# RWatch.net
KiCad netlist of a schematic drawn in EAGLE
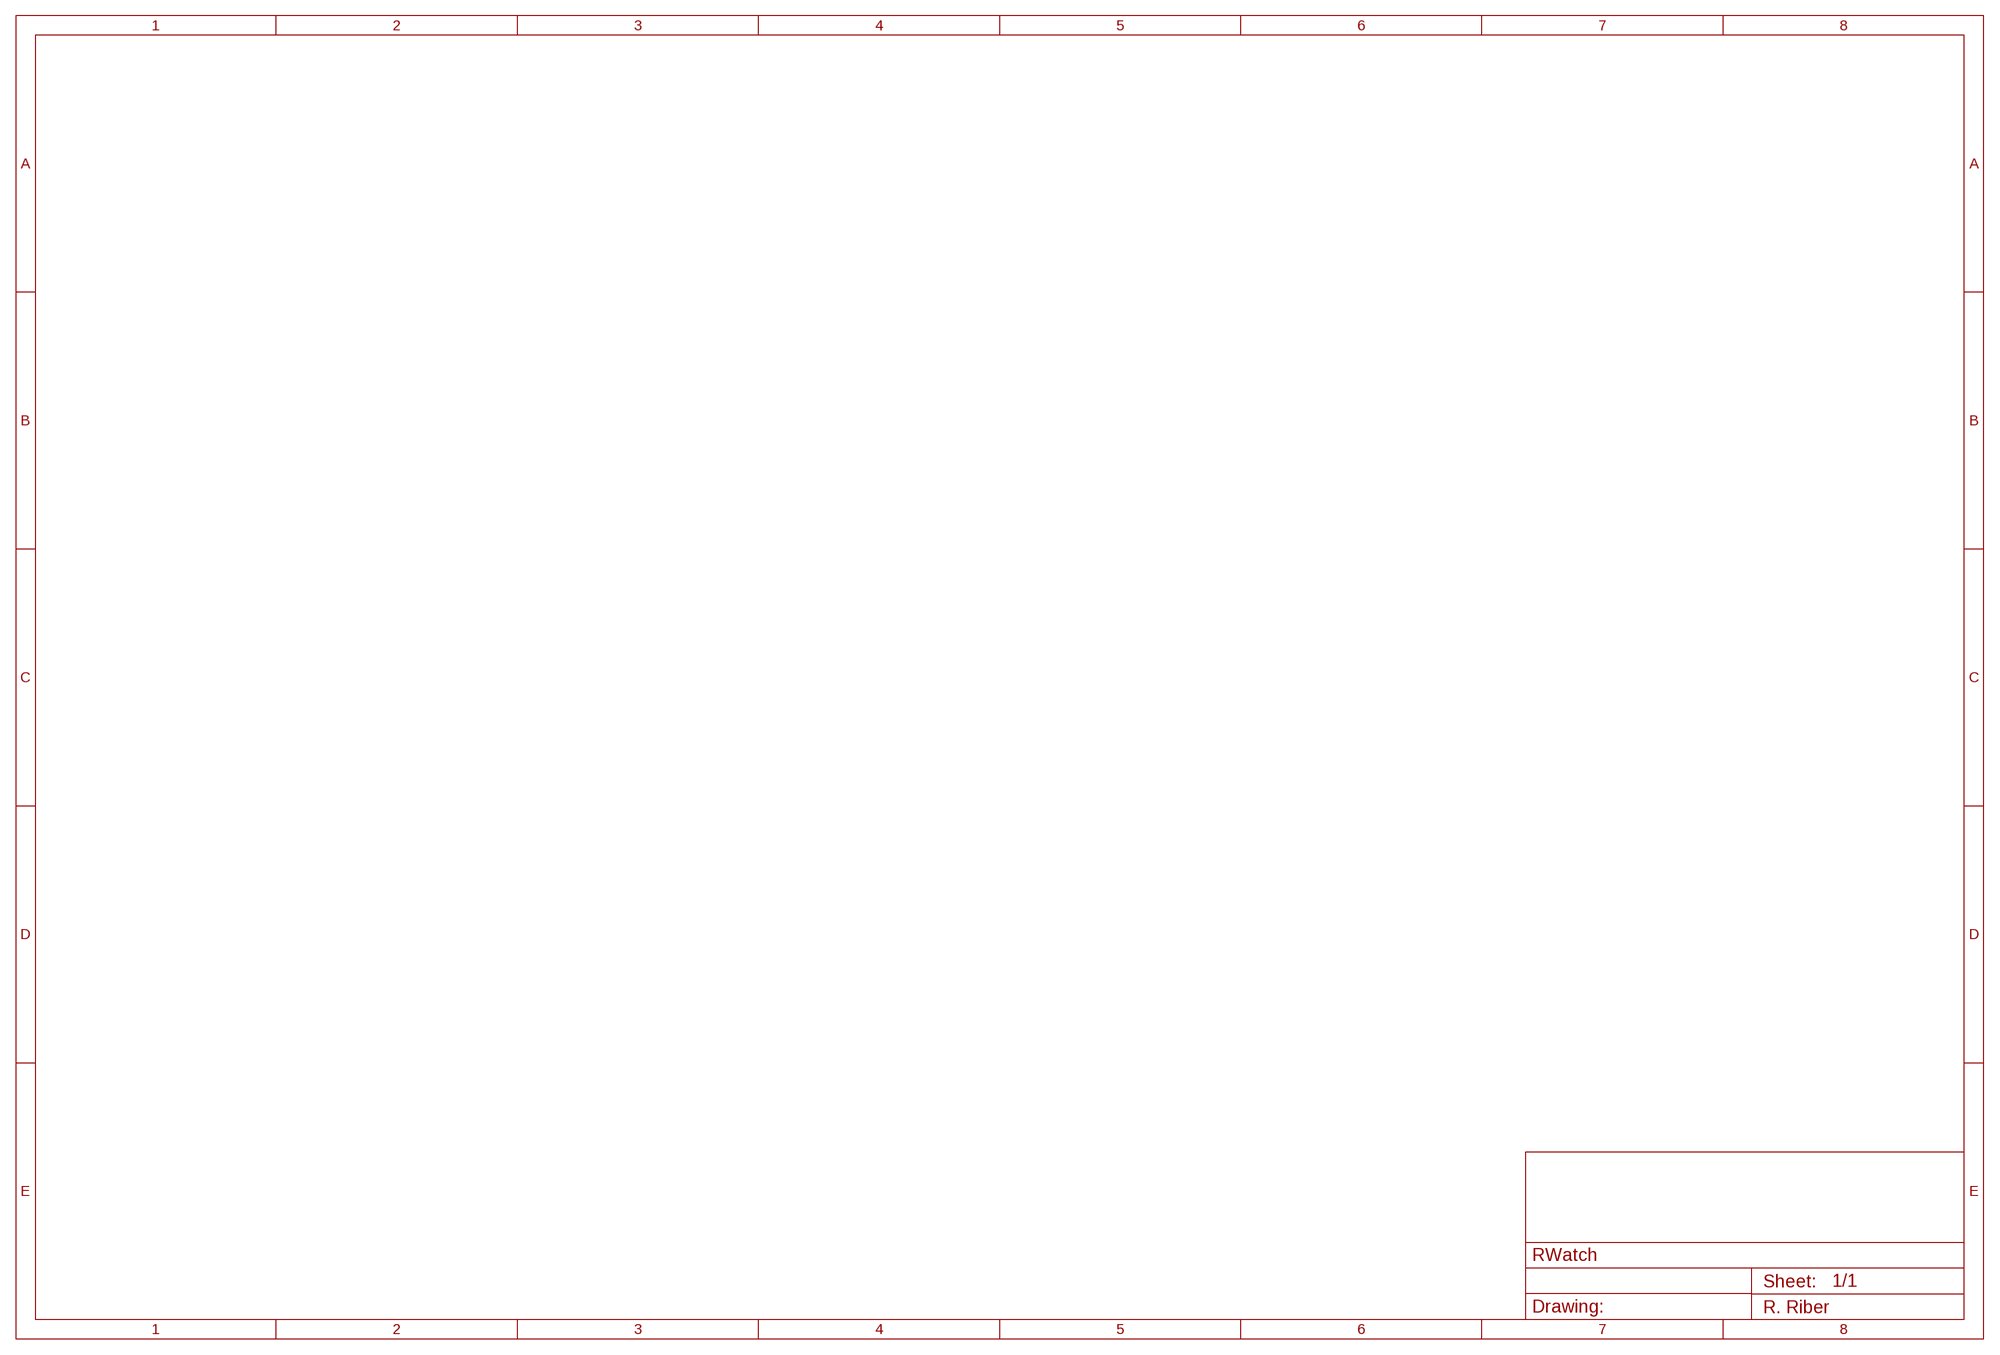
[diagram p0: schematic, sheet 1, part 1 of 2]
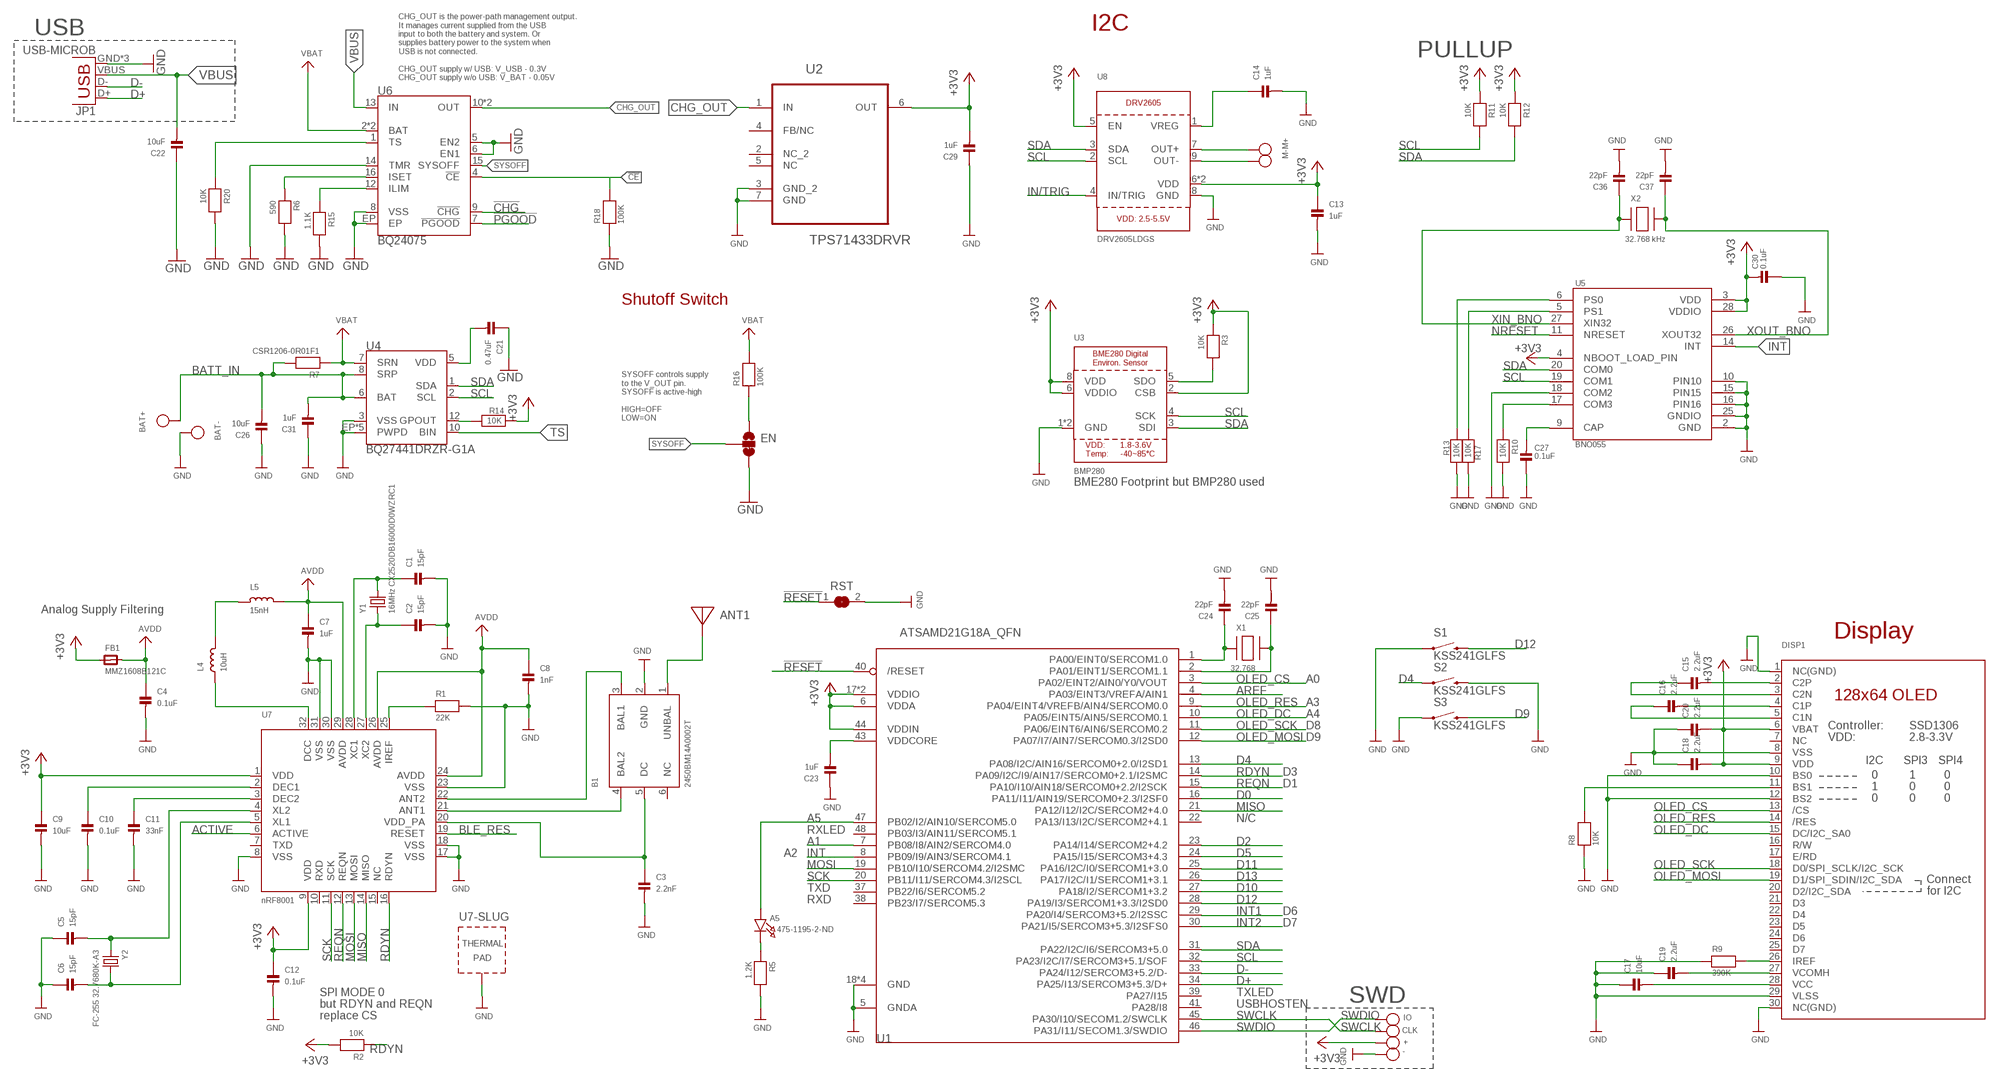
[diagram p1: schematic, sheet 1, part 2 of 2]

(export (version "E")
  (design (tool "Eeschema 10.0.6"))
  (components
    (comp (ref "+")
      (value "TESTPOINTROUND1.5MM")
      (footprint "eagle-import:TESTPOINT_ROUND_1.5MM")
      (libsource (lib "eagle-import") (part "TESTPOINTROUND1.5MM"))
    )
    (comp (ref "-")
      (value "TESTPOINTROUND1.5MM")
      (footprint "eagle-import:TESTPOINT_ROUND_1.5MM")
      (libsource (lib "eagle-import") (part "TESTPOINTROUND1.5MM"))
    )
    (comp (ref "A5")
      (value "475-1195-2-ND")
      (footprint "eagle-import:CHIPLED_0603_NOOUTLINE")
      (libsource (lib "eagle-import") (part "LED0603_NOOUTLINE"))
    )
    (comp (ref "ANT1")
      (value "ANTENNA_PCBNRF8001_1.6MM")
      (footprint "eagle-import:ANT_PCB_2.4GHZ_NRF8001_1.6MM_1OZ")
      (libsource (lib "eagle-import") (part "ANTENNA_PCBNRF8001_1.6MM"))
    )
    (comp (ref "B1")
      (value "2450BM14A0002T")
      (footprint "eagle-import:BALUN0603")
      (libsource (lib "eagle-import") (part "BALUN+LP_NORDIC"))
    )
    (comp (ref "BAT+")
      (value "TESTPOINTROUND2MM")
      (footprint "eagle-import:TESTPOINT_ROUND_2MM")
      (libsource (lib "eagle-import") (part "TESTPOINTROUND2MM"))
    )
    (comp (ref "BAT-")
      (value "TESTPOINTROUND2MM")
      (footprint "eagle-import:TESTPOINT_ROUND_2MM")
      (libsource (lib "eagle-import") (part "TESTPOINTROUND2MM"))
    )
    (comp (ref "C1")
      (value "15pF")
      (footprint "eagle-import:0402")
      (libsource (lib "eagle-import") (part "CAP_CERAMIC0402"))
    )
    (comp (ref "C2")
      (value "15pF")
      (footprint "eagle-import:0402")
      (libsource (lib "eagle-import") (part "CAP_CERAMIC0402"))
    )
    (comp (ref "C3")
      (value "2.2nF")
      (footprint "eagle-import:0402")
      (libsource (lib "eagle-import") (part "CAP_CERAMIC0402"))
    )
    (comp (ref "C4")
      (value "0.1uF")
      (footprint "eagle-import:0402")
      (libsource (lib "eagle-import") (part "CAP_CERAMIC0402"))
    )
    (comp (ref "C5")
      (value "15pF")
      (footprint "eagle-import:0402")
      (libsource (lib "eagle-import") (part "CAP_CERAMIC0402"))
    )
    (comp (ref "C6")
      (value "15pF")
      (footprint "eagle-import:0402")
      (libsource (lib "eagle-import") (part "CAP_CERAMIC0402"))
    )
    (comp (ref "C7")
      (value "1uF")
      (footprint "eagle-import:0402")
      (libsource (lib "eagle-import") (part "CAP_CERAMIC0402"))
    )
    (comp (ref "C8")
      (value "1nF")
      (footprint "eagle-import:0402")
      (libsource (lib "eagle-import") (part "CAP_CERAMIC0402"))
    )
    (comp (ref "C9")
      (value "10uF")
      (footprint "eagle-import:0402")
      (libsource (lib "eagle-import") (part "CAP_CERAMIC0402"))
    )
    (comp (ref "C10")
      (value "0.1uF")
      (footprint "eagle-import:0402")
      (libsource (lib "eagle-import") (part "CAP_CERAMIC0402"))
    )
    (comp (ref "C11")
      (value "33nF")
      (footprint "eagle-import:0402")
      (libsource (lib "eagle-import") (part "CAP_CERAMIC0402"))
    )
    (comp (ref "C12")
      (value "0.1uF")
      (footprint "eagle-import:0402")
      (libsource (lib "eagle-import") (part "CAP_CERAMIC0402"))
    )
    (comp (ref "C13")
      (value "1uF")
      (footprint "eagle-import:0402")
      (libsource (lib "eagle-import") (part "CAP_CERAMIC0402"))
    )
    (comp (ref "C14")
      (value "1uF")
      (footprint "eagle-import:0402")
      (libsource (lib "eagle-import") (part "CAP_CERAMIC0402"))
    )
    (comp (ref "C15")
      (value "2.2uF")
      (footprint "eagle-import:0402")
      (libsource (lib "eagle-import") (part "CAP_CERAMIC0402"))
    )
    (comp (ref "C16")
      (value "2.2uF")
      (footprint "eagle-import:0402")
      (libsource (lib "eagle-import") (part "CAP_CERAMIC0402"))
    )
    (comp (ref "C17")
      (value "10uF")
      (footprint "eagle-import:0603")
      (libsource (lib "eagle-import") (part "CAP_CERAMIC0603"))
    )
    (comp (ref "C18")
      (value "2.2uF")
      (footprint "eagle-import:0402")
      (libsource (lib "eagle-import") (part "CAP_CERAMIC0402"))
    )
    (comp (ref "C19")
      (value "2.2uF")
      (footprint "eagle-import:0402")
      (libsource (lib "eagle-import") (part "CAP_CERAMIC0402"))
    )
    (comp (ref "C20")
      (value "2.2uF")
      (footprint "eagle-import:0402")
      (libsource (lib "eagle-import") (part "CAP_CERAMIC0402"))
    )
    (comp (ref "C21")
      (value "0.47uF")
      (footprint "eagle-import:0402")
      (libsource (lib "eagle-import") (part "CAP_CERAMIC0402"))
    )
    (comp (ref "C22")
      (value "10uF")
      (footprint "eagle-import:0603")
      (libsource (lib "eagle-import") (part "CAP_CERAMIC0603"))
    )
    (comp (ref "C23")
      (value "1uF")
      (footprint "eagle-import:0402")
      (libsource (lib "eagle-import") (part "CAP_CERAMIC0402"))
    )
    (comp (ref "C24")
      (value "22pF")
      (footprint "eagle-import:0402")
      (libsource (lib "eagle-import") (part "CAP_CERAMIC0402"))
    )
    (comp (ref "C25")
      (value "22pF")
      (footprint "eagle-import:0402")
      (libsource (lib "eagle-import") (part "CAP_CERAMIC0402"))
    )
    (comp (ref "C26")
      (value "10uF")
      (footprint "eagle-import:0603")
      (libsource (lib "eagle-import") (part "CAP_CERAMIC0603"))
    )
    (comp (ref "C27")
      (value "0.1uF")
      (footprint "eagle-import:0402")
      (libsource (lib "eagle-import") (part "CAP_CERAMIC0402"))
    )
    (comp (ref "C29")
      (value "1uF")
      (footprint "eagle-import:0402")
      (libsource (lib "eagle-import") (part "CAP_CERAMIC0402"))
    )
    (comp (ref "C30")
      (value "0.1uF")
      (footprint "eagle-import:0402")
      (libsource (lib "eagle-import") (part "CAP_CERAMIC0402"))
    )
    (comp (ref "C31")
      (value "1uF")
      (footprint "eagle-import:0402")
      (libsource (lib "eagle-import") (part "CAP_CERAMIC0402"))
    )
    (comp (ref "C36")
      (value "22pF")
      (footprint "eagle-import:0402")
      (libsource (lib "eagle-import") (part "CAP_CERAMIC0402"))
    )
    (comp (ref "C37")
      (value "22pF")
      (footprint "eagle-import:0402")
      (libsource (lib "eagle-import") (part "CAP_CERAMIC0402"))
    )
    (comp (ref "CLK")
      (value "TESTPOINTROUND1.5MM")
      (footprint "eagle-import:TESTPOINT_ROUND_1.5MM")
      (libsource (lib "eagle-import") (part "TESTPOINTROUND1.5MM"))
    )
    (comp (ref "DISP1")
      (value "DISP_OLED_UG-2864HSWEG01")
      (footprint "eagle-import:UG-2864HSWEG01_1.3_WRAPAROUND")
      (libsource (lib "eagle-import") (part "DISP_OLED_UG-2864HSWEG01"))
    )
    (comp (ref "EN")
      (value "JUMPER-PAD-3-2OF3_NC_BY_TRACE_SMALL")
      (footprint "eagle-import:PAD-JUMPER-3-2OF3_NC_BY_TRACE_YES_SILK_FULL_BOX")
      (libsource (lib "eagle-import") (part "JUMPER-PAD-3-2OF3_NC_BY_TRACE_SMALL"))
    )
    (comp (ref "FB1")
      (value "MMZ1608B121C")
      (footprint "eagle-import:0805")
      (libsource (lib "eagle-import") (part "FERRITE0805"))
    )
    (comp (ref "IO")
      (value "TESTPOINTROUND1.5MM")
      (footprint "eagle-import:TESTPOINT_ROUND_1.5MM")
      (libsource (lib "eagle-import") (part "TESTPOINTROUND1.5MM"))
    )
    (comp (ref "JP1")
      (value "USB-MICROB")
      (footprint "eagle-import:USB-MICROB")
      (fields (field (name "MF") "FCI") (field (name "MPN") "10104110-0001LF"))
      (libsource (lib "eagle-import") (part "USB-MICROB"))
    )
    (comp (ref "L4")
      (value "10uH")
      (footprint "eagle-import:_0603")
      (libsource (lib "eagle-import") (part "INDUCTOR_0603"))
    )
    (comp (ref "L5")
      (value "15nH")
      (footprint "eagle-import:_0603")
      (libsource (lib "eagle-import") (part "INDUCTOR_0603"))
    )
    (comp (ref "M+")
      (value "TESTPOINTROUND2MM")
      (footprint "eagle-import:TESTPOINT_ROUND_2MM")
      (libsource (lib "eagle-import") (part "TESTPOINTROUND2MM"))
    )
    (comp (ref "M-")
      (value "TESTPOINTROUND2MM")
      (footprint "eagle-import:TESTPOINT_ROUND_2MM")
      (libsource (lib "eagle-import") (part "TESTPOINTROUND2MM"))
    )
    (comp (ref "R1")
      (value "22K")
      (footprint "eagle-import:0402")
      (libsource (lib "eagle-import") (part "RESISTOR0402"))
    )
    (comp (ref "R2")
      (value "10K")
      (footprint "eagle-import:0402")
      (libsource (lib "eagle-import") (part "RESISTOR0402"))
    )
    (comp (ref "R3")
      (value "10K")
      (footprint "eagle-import:0402")
      (fields (field (name "MF") "VISHAY") (field (name "MPN") "CRCW060310K0FKEA"))
      (libsource (lib "eagle-import") (part "RESISTOR0402"))
    )
    (comp (ref "R5")
      (value "1.2K")
      (footprint "eagle-import:0402")
      (fields (field (name "MF") "MULTICOMP") (field (name "MPN") "MC0063W06031221R"))
      (libsource (lib "eagle-import") (part "RESISTOR0402"))
    )
    (comp (ref "R6")
      (value "590")
      (footprint "eagle-import:0402")
      (fields (field (name "MF") "VISHAY") (field (name "MPN") "CRCW060310K0FKEA"))
      (libsource (lib "eagle-import") (part "RESISTOR0402"))
    )
    (comp (ref "R7")
      (value "CSR1206-0R01F1")
      (footprint "eagle-import:1206")
      (libsource (lib "eagle-import") (part "RESISTOR1206"))
    )
    (comp (ref "R8")
      (value "10K")
      (footprint "eagle-import:0402")
      (libsource (lib "eagle-import") (part "RESISTOR0402"))
    )
    (comp (ref "R9")
      (value "390K")
      (footprint "eagle-import:0402")
      (libsource (lib "eagle-import") (part "RESISTOR0402"))
    )
    (comp (ref "R10")
      (value "10K")
      (footprint "eagle-import:0402")
      (fields (field (name "MF") "VISHAY") (field (name "MPN") "CRCW060310K0FKEA"))
      (libsource (lib "eagle-import") (part "RESISTOR0402"))
    )
    (comp (ref "R11")
      (value "10K")
      (footprint "eagle-import:0402")
      (fields (field (name "MF") "VISHAY") (field (name "MPN") "CRCW060310K0FKEA"))
      (libsource (lib "eagle-import") (part "RESISTOR0402"))
    )
    (comp (ref "R12")
      (value "10K")
      (footprint "eagle-import:0402")
      (fields (field (name "MF") "VISHAY") (field (name "MPN") "CRCW060310K0FKEA"))
      (libsource (lib "eagle-import") (part "RESISTOR0402"))
    )
    (comp (ref "R13")
      (value "10K")
      (footprint "eagle-import:0402")
      (fields (field (name "MF") "VISHAY") (field (name "MPN") "CRCW060310K0FKEA"))
      (libsource (lib "eagle-import") (part "RESISTOR0402"))
    )
    (comp (ref "R14")
      (value "10K")
      (footprint "eagle-import:0402")
      (fields (field (name "MF") "VISHAY") (field (name "MPN") "CRCW060310K0FKEA"))
      (libsource (lib "eagle-import") (part "RESISTOR0402"))
    )
    (comp (ref "R15")
      (value "1.1K")
      (footprint "eagle-import:0402")
      (fields (field (name "MF") "VISHAY") (field (name "MPN") "CRCW060310K0FKEA"))
      (libsource (lib "eagle-import") (part "RESISTOR0402"))
    )
    (comp (ref "R16")
      (value "100K")
      (footprint "eagle-import:0402")
      (fields (field (name "MF") "MULTICOMP") (field (name "MPN") "MC0063W06031221R"))
      (libsource (lib "eagle-import") (part "RESISTOR0402"))
    )
    (comp (ref "R17")
      (value "10K")
      (footprint "eagle-import:0402")
      (fields (field (name "MF") "VISHAY") (field (name "MPN") "CRCW060310K0FKEA"))
      (libsource (lib "eagle-import") (part "RESISTOR0402"))
    )
    (comp (ref "R18")
      (value "100K")
      (footprint "eagle-import:0402")
      (fields (field (name "MF") "MULTICOMP") (field (name "MPN") "MC0063W06031221R"))
      (libsource (lib "eagle-import") (part "RESISTOR0402"))
    )
    (comp (ref "R20")
      (value "10K")
      (footprint "eagle-import:0402")
      (fields (field (name "MF") "VISHAY") (field (name "MPN") "CRCW060310K0FKEA"))
      (libsource (lib "eagle-import") (part "RESISTOR0402"))
    )
    (comp (ref "RST")
      (value "SOLDERJUMPERREFLOW")
      (footprint "eagle-import:SOLDERJUMPER_REFLOW")
      (libsource (lib "eagle-import") (part "SOLDERJUMPERREFLOW"))
    )
    (comp (ref "S1")
      (value "KSS241GLFS")
      (footprint "eagle-import:KSS241GLFS")
      (libsource (lib "eagle-import") (part "KSS241GLFS"))
    )
    (comp (ref "S2")
      (value "KSS241GLFS")
      (footprint "eagle-import:KSS241GLFS")
      (libsource (lib "eagle-import") (part "KSS241GLFS"))
    )
    (comp (ref "S3")
      (value "KSS241GLFS")
      (footprint "eagle-import:KSS241GLFS")
      (libsource (lib "eagle-import") (part "KSS241GLFS"))
    )
    (comp (ref "U1")
      (value "ATSAMD21G18A_QFN")
      (footprint "eagle-import:TQFN48_7MM")
      (libsource (lib "eagle-import") (part "ATSAMD21G18A_QFN"))
    )
    (comp (ref "U2")
      (value "TPS71433DRVR")
      (footprint "eagle-import:SON65P200X200X80-7N")
      (fields (field (name "MF") "Texas Instruments"))
      (libsource (lib "eagle-import") (part "TPS71433DRVR"))
    )
    (comp (ref "U3")
      (value "BMP280")
      (footprint "eagle-import:BME280")
      (libsource (lib "eagle-import") (part "BME280"))
    )
    (comp (ref "U4")
      (value "BQ27441DRZR-G1A")
      (footprint "eagle-import:PDSO-N12")
      (libsource (lib "eagle-import") (part "BQ27441-G1"))
    )
    (comp (ref "U5")
      (value "BNO055")
      (footprint "eagle-import:LGA28R50P4X10_380X520X100")
      (fields (field (name "MF") "Bosch"))
      (libsource (lib "eagle-import") (part "BNO055"))
    )
    (comp (ref "U6")
      (value "BQ24075")
      (footprint "eagle-import:PVQFN-N16")
      (libsource (lib "eagle-import") (part "BQ24075"))
    )
    (comp (ref "U7")
      (value "nRF8001")
      (footprint "eagle-import:QFN32_5MM")
      (libsource (lib "eagle-import") (part "NRF8001"))
    )
    (comp (ref "U8")
      (value "DRV2605LDGS")
      (footprint "eagle-import:PSOP10")
      (libsource (lib "eagle-import") (part "DRV2605_SOP"))
    )
    (comp (ref "X1")
      (value "32.768")
      (footprint "eagle-import:XTAL3215")
      (libsource (lib "eagle-import") (part "XTAL-3.2X1.5"))
    )
    (comp (ref "X2")
      (value "32.768 kHz")
      (footprint "eagle-import:XTAL3215")
      (libsource (lib "eagle-import") (part "XTAL-3.2X1.5"))
    )
    (comp (ref "Y1")
      (value "16MHz CX2520DB16000D0WZRC1")
      (footprint "eagle-import:CRYSTAL_2.5X2")
      (libsource (lib "eagle-import") (part "CRYSTAL2.5X2.0MM"))
    )
    (comp (ref "Y2")
      (value "FC-255 32.7680K-A3")
      (footprint "eagle-import:CRYSTAL_4.9X1.8")
      (libsource (lib "eagle-import") (part "CRYSTALTHIN32K"))
    )
  )
  (nets
    (net (code "1") (name "+3V3") (class "Default")
      (node (ref "+") (pin "P$1") (pinfunction "P$1_P$1") (pintype "bidirectional"))
      (node (ref "C12") (pin "1") (pinfunction "P$1_1") (pintype "passive"))
      (node (ref "C13") (pin "1") (pinfunction "P$1_1") (pintype "passive"))
      (node (ref "C18") (pin "2") (pinfunction "P$2_2") (pintype "passive"))
      (node (ref "C20") (pin "2") (pinfunction "P$2_2") (pintype "passive"))
      (node (ref "C29") (pin "2") (pinfunction "P$2_2") (pintype "passive"))
      (node (ref "C30") (pin "2") (pinfunction "P$2_2") (pintype "passive"))
      (node (ref "C9") (pin "1") (pinfunction "P$1_1") (pintype "passive"))
      (node (ref "DISP1") (pin "6") (pinfunction "VBAT_6") (pintype "input"))
      (node (ref "DISP1") (pin "9") (pinfunction "VDD_9") (pintype "power_in"))
      (node (ref "FB1") (pin "1") (pinfunction "P$1_1") (pintype "passive"))
      (node (ref "R11") (pin "1") (pinfunction "1_1") (pintype "passive"))
      (node (ref "R12") (pin "1") (pinfunction "1_1") (pintype "passive"))
      (node (ref "R14") (pin "1") (pinfunction "1_1") (pintype "passive"))
      (node (ref "R2") (pin "2") (pinfunction "2_2") (pintype "passive"))
      (node (ref "R3") (pin "1") (pinfunction "1_1") (pintype "passive"))
      (node (ref "U1") (pin "17") (pinfunction "VDDIO_17") (pintype "power_in"))
      (node (ref "U1") (pin "36") (pinfunction "VDDIO_36") (pintype "power_in"))
      (node (ref "U1") (pin "44") (pinfunction "VDDIN_44") (pintype "power_in"))
      (node (ref "U1") (pin "6") (pinfunction "VDDA_6") (pintype "power_in"))
      (node (ref "U2") (pin "6") (pinfunction "OUT_6") (pintype "output"))
      (node (ref "U3") (pin "2") (pinfunction "CSB_2") (pintype "input"))
      (node (ref "U3") (pin "6") (pinfunction "VDDIO_6") (pintype "power_in"))
      (node (ref "U3") (pin "8") (pinfunction "VDD_8") (pintype "power_in"))
      (node (ref "U5") (pin "28") (pinfunction "VDDIO_28") (pintype "power_in"))
      (node (ref "U5") (pin "3") (pinfunction "VDD_3") (pintype "power_in"))
      (node (ref "U5") (pin "4") (pinfunction "NBOOT_LOAD_PIN_4") (pintype "bidirectional"))
      (node (ref "U7") (pin "1") (pinfunction "VDD_1") (pintype "power_in"))
      (node (ref "U7") (pin "9") (pinfunction "VDD_9") (pintype "power_in"))
      (node (ref "U8") (pin "10") (pinfunction "VDD_10") (pintype "power_in"))
      (node (ref "U8") (pin "5") (pinfunction "EN_5") (pintype "input"))
      (node (ref "U8") (pin "6") (pinfunction "VDD_6") (pintype "power_in"))
    )
    (net (code "2") (name "/A1") (class "Default")
      (node (ref "U1") (pin "7") (pinfunction "PB08/I8/AIN2/SERCOM4.0_7") (pintype "bidirectional"))
    )
    (net (code "3") (name "/A5") (class "Default")
      (node (ref "A5") (pin "A") (pinfunction "A_A") (pintype "passive"))
      (node (ref "U1") (pin "47") (pinfunction "PB02/I2/AIN10/SERCOM5.0_47") (pintype "bidirectional"))
    )
    (net (code "4") (name "/ACTIVE") (class "Default")
      (node (ref "U7") (pin "6") (pinfunction "ACTIVE_6") (pintype "output"))
    )
    (net (code "5") (name "/AREF") (class "Default")
      (node (ref "U1") (pin "4") (pinfunction "PA03/EINT3/VREFA/AIN1_4") (pintype "bidirectional"))
    )
    (net (code "6") (name "/BATT_IN") (class "Default")
      (node (ref "BAT+") (pin "P$1") (pinfunction "P$1_P$1") (pintype "bidirectional"))
      (node (ref "C26") (pin "2") (pinfunction "P$2_2") (pintype "passive"))
      (node (ref "C31") (pin "2") (pinfunction "P$2_2") (pintype "passive"))
      (node (ref "R7") (pin "2") (pinfunction "2_2") (pintype "passive"))
      (node (ref "U4") (pin "6") (pinfunction "BAT_6") (pintype "bidirectional"))
      (node (ref "U4") (pin "8") (pinfunction "SRP_8") (pintype "bidirectional"))
    )
    (net (code "7") (name "/BLE_RES") (class "Default")
      (node (ref "U7") (pin "19") (pinfunction "RESET_19") (pintype "input"))
    )
    (net (code "8") (name "/D+") (class "Default")
      (node (ref "JP1") (pin "D+") (pinfunction "D+_D+") (pintype "bidirectional"))
      (node (ref "U1") (pin "34") (pinfunction "PA25/I13/SERCOM3+5.3/D+_34") (pintype "bidirectional"))
    )
    (net (code "9") (name "/D-") (class "Default")
      (node (ref "JP1") (pin "D-") (pinfunction "D-_D-") (pintype "bidirectional"))
      (node (ref "U1") (pin "33") (pinfunction "PA24/I12/SERCOM3+5.2/D-_33") (pintype "bidirectional"))
    )
    (net (code "10") (name "/D0") (class "Default")
      (node (ref "U1") (pin "16") (pinfunction "PA11/I11/AIN19/SERCOM0+2.3/I2SF0_16") (pintype "bidirectional"))
    )
    (net (code "11") (name "/D2") (class "Default")
      (node (ref "U1") (pin "23") (pinfunction "PA14/I14/SERCOM2+4.2_23") (pintype "bidirectional"))
    )
    (net (code "12") (name "/D4") (class "Default")
      (node (ref "S2") (pin "1") (pinfunction "1_1") (pintype "passive"))
      (node (ref "U1") (pin "13") (pinfunction "PA08/I2C/AIN16/SERCOM0+2.0/I2SD1_13") (pintype "bidirectional"))
    )
    (net (code "13") (name "/D5") (class "Default")
      (node (ref "U1") (pin "24") (pinfunction "PA15/I15/SERCOM3+4.3_24") (pintype "bidirectional"))
    )
    (net (code "14") (name "/D9") (class "Default")
      (node (ref "S3") (pin "2") (pinfunction "2_2") (pintype "passive"))
    )
    (net (code "15") (name "/D10") (class "Default")
      (node (ref "U1") (pin "27") (pinfunction "PA18/I2/SERCOM1+3.2_27") (pintype "bidirectional"))
    )
    (net (code "16") (name "/D11") (class "Default")
      (node (ref "U1") (pin "25") (pinfunction "PA16/I2C/I0/SERCOM1+3.0_25") (pintype "bidirectional"))
    )
    (net (code "17") (name "/D12") (class "Default")
      (node (ref "S1") (pin "2") (pinfunction "2_2") (pintype "passive"))
      (node (ref "U1") (pin "28") (pinfunction "PA19/I3/SERCOM1+3.3/I2SD0_28") (pintype "bidirectional"))
    )
    (net (code "18") (name "/D13") (class "Default")
      (node (ref "U1") (pin "26") (pinfunction "PA17/I2C/I1/SERCOM1+3.1_26") (pintype "bidirectional"))
    )
    (net (code "19") (name "/INT1") (class "Default")
      (node (ref "U1") (pin "29") (pinfunction "PA20/I4/SERCOM3+5.2/I2SSC_29") (pintype "bidirectional"))
    )
    (net (code "20") (name "/INT2") (class "Default")
      (node (ref "U1") (pin "30") (pinfunction "PA21/I5/SERCOM3+5.3/I2SFS0_30") (pintype "bidirectional"))
    )
    (net (code "21") (name "/IN{slash}TRIG") (class "Default")
      (node (ref "U8") (pin "4") (pinfunction "IN/TRIG_4") (pintype "input"))
    )
    (net (code "22") (name "/MISO") (class "Default")
      (node (ref "U1") (pin "21") (pinfunction "PA12/I12/I2C/SERCOM2+4.0_21") (pintype "bidirectional"))
      (node (ref "U7") (pin "14") (pinfunction "MISO_14") (pintype "output"))
    )
    (net (code "23") (name "/MOSI") (class "Default")
      (node (ref "U1") (pin "19") (pinfunction "PB10/I10/SERCOM4.2/I2SMC_19") (pintype "bidirectional"))
      (node (ref "U7") (pin "13") (pinfunction "MOSI_13") (pintype "input"))
    )
    (net (code "24") (name "/NRESET") (class "Default")
      (node (ref "U5") (pin "11") (pinfunction "NRESET_11") (pintype "input"))
    )
    (net (code "25") (name "/OLED_CS") (class "Default")
      (node (ref "DISP1") (pin "13") (pinfunction "/CS_13") (pintype "input"))
      (node (ref "U1") (pin "3") (pinfunction "PA02/EINT2/AIN0/Y0/VOUT_3") (pintype "bidirectional"))
    )
    (net (code "26") (name "/OLED_DC") (class "Default")
      (node (ref "DISP1") (pin "15") (pinfunction "DC/I2C_SA0_15") (pintype "input"))
      (node (ref "U1") (pin "10") (pinfunction "PA05/EINT5/AIN5/SERCOM0.1_10") (pintype "bidirectional"))
    )
    (net (code "27") (name "/OLED_MOSI") (class "Default")
      (node (ref "DISP1") (pin "19") (pinfunction "D1/SPI_SDIN/I2C_SDA_19") (pintype "bidirectional"))
      (node (ref "U1") (pin "12") (pinfunction "PA07/I7/AIN7/SERCOM0.3/I2SD0_12") (pintype "bidirectional"))
    )
    (net (code "28") (name "/OLED_RES") (class "Default")
      (node (ref "DISP1") (pin "14") (pinfunction "/RES_14") (pintype "input"))
      (node (ref "U1") (pin "9") (pinfunction "PA04/EINT4/VREFB/AIN4/SERCOM0.0_9") (pintype "bidirectional"))
    )
    (net (code "29") (name "/OLED_SCK") (class "Default")
      (node (ref "DISP1") (pin "18") (pinfunction "D0/SPI_SCLK/I2C_SCK_18") (pintype "bidirectional"))
      (node (ref "U1") (pin "11") (pinfunction "PA06/EINT6/AIN6/SERCOM0.2_11") (pintype "bidirectional"))
    )
    (net (code "30") (name "/RDYN") (class "Default")
      (node (ref "R2") (pin "1") (pinfunction "1_1") (pintype "passive"))
      (node (ref "U1") (pin "14") (pinfunction "PA09/I2C/I9/AIN17/SERCOM0+2.1/I2SMC_14") (pintype "bidirectional"))
      (node (ref "U7") (pin "16") (pinfunction "RDYN_16") (pintype "output"))
    )
    (net (code "31") (name "/REQN") (class "Default")
      (node (ref "U1") (pin "15") (pinfunction "PA10/I10/AIN18/SERCOM0+2.2/I2SCK_15") (pintype "bidirectional"))
      (node (ref "U7") (pin "12") (pinfunction "REQN_12") (pintype "input"))
    )
    (net (code "32") (name "/SCK") (class "Default")
      (node (ref "U1") (pin "20") (pinfunction "PB11/I11/SERCOM4.3/I2SCL_20") (pintype "bidirectional"))
      (node (ref "U7") (pin "11") (pinfunction "SCK_11") (pintype "input"))
    )
    (net (code "33") (name "/SCL") (class "Default")
      (node (ref "R11") (pin "2") (pinfunction "2_2") (pintype "passive"))
      (node (ref "U1") (pin "32") (pinfunction "PA23/I2C/I7/SERCOM3+5.1/SOF_32") (pintype "bidirectional"))
      (node (ref "U3") (pin "4") (pinfunction "SCK_4") (pintype "input"))
      (node (ref "U4") (pin "2") (pinfunction "SCL_2") (pintype "bidirectional"))
      (node (ref "U5") (pin "19") (pinfunction "COM1_19") (pintype "bidirectional"))
      (node (ref "U8") (pin "2") (pinfunction "SCL_2") (pintype "input"))
    )
    (net (code "34") (name "/SDA") (class "Default")
      (node (ref "R12") (pin "2") (pinfunction "2_2") (pintype "passive"))
      (node (ref "U1") (pin "31") (pinfunction "PA22/I2C/I6/SERCOM3+5.0_31") (pintype "bidirectional"))
      (node (ref "U3") (pin "3") (pinfunction "SDI_3") (pintype "input"))
      (node (ref "U4") (pin "1") (pinfunction "SDA_1") (pintype "bidirectional"))
      (node (ref "U5") (pin "20") (pinfunction "COM0_20") (pintype "bidirectional"))
      (node (ref "U8") (pin "3") (pinfunction "SDA_3") (pintype "bidirectional"))
    )
    (net (code "35") (name "/SWCLK") (class "Default")
      (node (ref "CLK") (pin "P$1") (pinfunction "P$1_P$1") (pintype "bidirectional"))
      (node (ref "U1") (pin "45") (pinfunction "PA30/I10/SECOM1.2/SWCLK_45") (pintype "bidirectional"))
    )
    (net (code "36") (name "/SWDIO") (class "Default")
      (node (ref "IO") (pin "P$1") (pinfunction "P$1_P$1") (pintype "bidirectional"))
      (node (ref "U1") (pin "46") (pinfunction "PA31/I11/SECOM1.3/SWDIO_46") (pintype "bidirectional"))
    )
    (net (code "37") (name "/XIN_BNO") (class "Default")
      (node (ref "C36") (pin "1") (pinfunction "P$1_1") (pintype "passive"))
      (node (ref "U5") (pin "27") (pinfunction "XIN32_27") (pintype "input"))
      (node (ref "X2") (pin "P$1") (pinfunction "P$1_P$1") (pintype "bidirectional"))
    )
    (net (code "38") (name "/XOUT_BNO") (class "Default")
      (node (ref "C37") (pin "1") (pinfunction "P$1_1") (pintype "passive"))
      (node (ref "U5") (pin "26") (pinfunction "XOUT32_26") (pintype "output"))
      (node (ref "X2") (pin "P$2") (pinfunction "P$2_P$2") (pintype "bidirectional"))
    )
    (net (code "39") (name "/~{CE}") (class "Default")
      (node (ref "R18") (pin "2") (pinfunction "2_2") (pintype "passive"))
      (node (ref "U6") (pin "4") (pinfunction "~{CE}_4") (pintype "bidirectional"))
    )
    (net (code "40") (name "/~{CHG}") (class "Default")
      (node (ref "U6") (pin "9") (pinfunction "~{CHG}_9") (pintype "bidirectional"))
    )
    (net (code "41") (name "/~{PGOOD}") (class "Default")
      (node (ref "U6") (pin "7") (pinfunction "~{PGOOD}_7") (pintype "bidirectional"))
    )
    (net (code "42") (name "/~{RESET}") (class "Default")
      (node (ref "RST") (pin "1") (pinfunction "1_1") (pintype "passive"))
      (node (ref "U1") (pin "40") (pinfunction "/RESET_40") (pintype "bidirectional"))
    )
    (net (code "43") (name "AVDD") (class "Default")
      (node (ref "C4") (pin "1") (pinfunction "P$1_1") (pintype "passive"))
      (node (ref "C7") (pin "1") (pinfunction "P$1_1") (pintype "passive"))
      (node (ref "C8") (pin "1") (pinfunction "P$1_1") (pintype "passive"))
      (node (ref "FB1") (pin "2") (pinfunction "P$2_2") (pintype "passive"))
      (node (ref "L5") (pin "2") (pinfunction "2_2") (pintype "passive"))
      (node (ref "U7") (pin "24") (pinfunction "AVDD_24") (pintype "power_in"))
      (node (ref "U7") (pin "26") (pinfunction "AVDD_26") (pintype "power_in"))
      (node (ref "U7") (pin "29") (pinfunction "AVDD_29") (pintype "power_in"))
    )
    (net (code "44") (name "CHG_OUT") (class "Default")
      (node (ref "U2") (pin "1") (pinfunction "IN_1") (pintype "power_in"))
      (node (ref "U6") (pin "10") (pinfunction "OUT_10") (pintype "bidirectional"))
      (node (ref "U6") (pin "11") (pinfunction "OUT_11") (pintype "bidirectional"))
    )
    (net (code "45") (name "GND") (class "Default")
      (node (ref "-") (pin "P$1") (pinfunction "P$1_P$1") (pintype "bidirectional"))
      (node (ref "B1") (pin "2") (pinfunction "GND_2") (pintype "power_in"))
      (node (ref "BAT-") (pin "P$1") (pinfunction "P$1_P$1") (pintype "bidirectional"))
      (node (ref "C1") (pin "2") (pinfunction "P$2_2") (pintype "passive"))
      (node (ref "C10") (pin "2") (pinfunction "P$2_2") (pintype "passive"))
      (node (ref "C11") (pin "2") (pinfunction "P$2_2") (pintype "passive"))
      (node (ref "C12") (pin "2") (pinfunction "P$2_2") (pintype "passive"))
      (node (ref "C13") (pin "2") (pinfunction "P$2_2") (pintype "passive"))
      (node (ref "C14") (pin "2") (pinfunction "P$2_2") (pintype "passive"))
      (node (ref "C17") (pin "1") (pinfunction "P$1_1") (pintype "passive"))
      (node (ref "C18") (pin "1") (pinfunction "P$1_1") (pintype "passive"))
      (node (ref "C19") (pin "1") (pinfunction "P$1_1") (pintype "passive"))
      (node (ref "C2") (pin "2") (pinfunction "P$2_2") (pintype "passive"))
      (node (ref "C20") (pin "1") (pinfunction "P$1_1") (pintype "passive"))
      (node (ref "C21") (pin "1") (pinfunction "P$1_1") (pintype "passive"))
      (node (ref "C22") (pin "1") (pinfunction "P$1_1") (pintype "passive"))
      (node (ref "C23") (pin "1") (pinfunction "P$1_1") (pintype "passive"))
      (node (ref "C24") (pin "2") (pinfunction "P$2_2") (pintype "passive"))
      (node (ref "C25") (pin "2") (pinfunction "P$2_2") (pintype "passive"))
      (node (ref "C26") (pin "1") (pinfunction "P$1_1") (pintype "passive"))
      (node (ref "C27") (pin "1") (pinfunction "P$1_1") (pintype "passive"))
      (node (ref "C29") (pin "1") (pinfunction "P$1_1") (pintype "passive"))
      (node (ref "C3") (pin "2") (pinfunction "P$2_2") (pintype "passive"))
      (node (ref "C30") (pin "1") (pinfunction "P$1_1") (pintype "passive"))
      (node (ref "C31") (pin "1") (pinfunction "P$1_1") (pintype "passive"))
      (node (ref "C36") (pin "2") (pinfunction "P$2_2") (pintype "passive"))
      (node (ref "C37") (pin "2") (pinfunction "P$2_2") (pintype "passive"))
      (node (ref "C4") (pin "2") (pinfunction "P$2_2") (pintype "passive"))
      (node (ref "C5") (pin "1") (pinfunction "P$1_1") (pintype "passive"))
      (node (ref "C6") (pin "1") (pinfunction "P$1_1") (pintype "passive"))
      (node (ref "C7") (pin "2") (pinfunction "P$2_2") (pintype "passive"))
      (node (ref "C8") (pin "2") (pinfunction "P$2_2") (pintype "passive"))
      (node (ref "C9") (pin "2") (pinfunction "P$2_2") (pintype "passive"))
      (node (ref "DISP1") (pin "1") (pinfunction "NC(GND)_1") (pintype "input"))
      (node (ref "DISP1") (pin "10") (pinfunction "BS0_10") (pintype "input"))
      (node (ref "DISP1") (pin "12") (pinfunction "BS2_12") (pintype "input"))
      (node (ref "DISP1") (pin "29") (pinfunction "VLSS_29") (pintype "power_in"))
      (node (ref "DISP1") (pin "30") (pinfunction "NC(GND)_30") (pintype "input"))
      (node (ref "DISP1") (pin "8") (pinfunction "VSS_8") (pintype "power_in"))
      (node (ref "EN") (pin "3") (pinfunction "3_3") (pintype "passive"))
      (node (ref "JP1") (pin "GND") (pinfunction "GND_GND") (pintype "bidirectional"))
      (node (ref "JP1") (pin "MT1") (pinfunction "GND_MT1") (pintype "bidirectional"))
      (node (ref "JP1") (pin "MT2") (pinfunction "GND_MT2") (pintype "bidirectional"))
      (node (ref "R1") (pin "2") (pinfunction "2_2") (pintype "passive"))
      (node (ref "R10") (pin "2") (pinfunction "2_2") (pintype "passive"))
      (node (ref "R13") (pin "2") (pinfunction "2_2") (pintype "passive"))
      (node (ref "R15") (pin "2") (pinfunction "2_2") (pintype "passive"))
      (node (ref "R17") (pin "2") (pinfunction "2_2") (pintype "passive"))
      (node (ref "R18") (pin "1") (pinfunction "1_1") (pintype "passive"))
      (node (ref "R20") (pin "2") (pinfunction "2_2") (pintype "passive"))
      (node (ref "R5") (pin "2") (pinfunction "2_2") (pintype "passive"))
      (node (ref "R6") (pin "2") (pinfunction "2_2") (pintype "passive"))
      (node (ref "R8") (pin "1") (pinfunction "1_1") (pintype "passive"))
      (node (ref "R9") (pin "1") (pinfunction "1_1") (pintype "passive"))
      (node (ref "RST") (pin "2") (pinfunction "2_2") (pintype "passive"))
      (node (ref "S1") (pin "1") (pinfunction "1_1") (pintype "passive"))
      (node (ref "S2") (pin "2") (pinfunction "2_2") (pintype "passive"))
      (node (ref "S3") (pin "1") (pinfunction "1_1") (pintype "passive"))
      (node (ref "U1") (pin "18") (pinfunction "GND_18") (pintype "power_in"))
      (node (ref "U1") (pin "35") (pinfunction "GND_35") (pintype "power_in"))
      (node (ref "U1") (pin "42") (pinfunction "GND_42") (pintype "power_in"))
      (node (ref "U1") (pin "5") (pinfunction "GNDA_5") (pintype "power_in"))
      (node (ref "U1") (pin "THERMAL") (pinfunction "GND_THERMAL") (pintype "power_in"))
      (node (ref "U2") (pin "3") (pinfunction "GND_2_3") (pintype "passive"))
      (node (ref "U2") (pin "7") (pinfunction "GND_7") (pintype "passive"))
      (node (ref "U3") (pin "1") (pinfunction "GND_1") (pintype "power_in"))
      (node (ref "U3") (pin "7") (pinfunction "GND_7") (pintype "power_in"))
      (node (ref "U4") (pin "3") (pinfunction "VSS_3") (pintype "bidirectional"))
      (node (ref "U4") (pin "EP") (pinfunction "PWPD_EP") (pintype "bidirectional"))
      (node (ref "U4") (pin "EP1") (pinfunction "PWPD_EP1") (pintype "bidirectional"))
      (node (ref "U4") (pin "EP2") (pinfunction "PWPD_EP2") (pintype "bidirectional"))
      (node (ref "U4") (pin "EP3") (pinfunction "PWPD_EP3") (pintype "bidirectional"))
      (node (ref "U4") (pin "EP4") (pinfunction "PWPD_EP4") (pintype "bidirectional"))
      (node (ref "U5") (pin "10") (pinfunction "PIN10_10") (pintype "power_in"))
      (node (ref "U5") (pin "15") (pinfunction "PIN15_15") (pintype "power_in"))
      (node (ref "U5") (pin "16") (pinfunction "PIN16_16") (pintype "power_in"))
      (node (ref "U5") (pin "18") (pinfunction "COM2_18") (pintype "bidirectional"))
      (node (ref "U5") (pin "2") (pinfunction "GND_2") (pintype "power_in"))
      (node (ref "U5") (pin "25") (pinfunction "GNDIO_25") (pintype "power_in"))
      (node (ref "U6") (pin "14") (pinfunction "TMR_14") (pintype "bidirectional"))
      (node (ref "U6") (pin "5") (pinfunction "EN2_5") (pintype "bidirectional"))
      (node (ref "U6") (pin "6") (pinfunction "EN1_6") (pintype "bidirectional"))
      (node (ref "U6") (pin "8") (pinfunction "VSS_8") (pintype "bidirectional"))
      (node (ref "U6") (pin "EP") (pinfunction "EP_EP") (pintype "bidirectional"))
      (node (ref "U7") (pin "17") (pinfunction "VSS_17") (pintype "power_in"))
      (node (ref "U7") (pin "18") (pinfunction "VSS_18") (pintype "power_in"))
      (node (ref "U7") (pin "23") (pinfunction "VSS_23") (pintype "power_in"))
      (node (ref "U7") (pin "30") (pinfunction "VSS_30") (pintype "power_in"))
      (node (ref "U7") (pin "31") (pinfunction "VSS_31") (pintype "power_in"))
      (node (ref "U7") (pin "33") (pinfunction "TP_33") (pintype "power_in"))
      (node (ref "U7") (pin "8") (pinfunction "VSS_8") (pintype "power_in"))
      (node (ref "U8") (pin "8") (pinfunction "GND_8") (pintype "power_in"))
    )
    (net (code "46") (name "INT") (class "Default")
      (node (ref "U1") (pin "8") (pinfunction "PB09/I9/AIN3/SERCOM4.1_8") (pintype "bidirectional"))
      (node (ref "U5") (pin "14") (pinfunction "INT_14") (pintype "output"))
    )
    (net (code "47") (name "Net-(A5-PadC)") (class "Default")
      (node (ref "A5") (pin "C") (pinfunction "C_C") (pintype "passive"))
      (node (ref "R5") (pin "1") (pinfunction "1_1") (pintype "passive"))
    )
    (net (code "48") (name "Net-(ANT1-P$1)") (class "Default")
      (node (ref "ANT1") (pin "FEED") (pinfunction "P$1_FEED") (pintype "passive"))
      (node (ref "B1") (pin "1") (pinfunction "UNBAL_1") (pintype "bidirectional"))
    )
    (net (code "49") (name "Net-(B1-BAL1)") (class "Default")
      (node (ref "B1") (pin "3") (pinfunction "BAL1_3") (pintype "bidirectional"))
      (node (ref "U7") (pin "22") (pinfunction "ANT2_22") (pintype "bidirectional"))
    )
    (net (code "50") (name "Net-(B1-BAL2)") (class "Default")
      (node (ref "B1") (pin "4") (pinfunction "BAL2_4") (pintype "bidirectional"))
      (node (ref "U7") (pin "21") (pinfunction "ANT1_21") (pintype "bidirectional"))
    )
    (net (code "51") (name "Net-(B1-DC)") (class "Default")
      (node (ref "B1") (pin "5") (pinfunction "DC_5") (pintype "bidirectional"))
      (node (ref "C3") (pin "1") (pinfunction "P$1_1") (pintype "passive"))
      (node (ref "U7") (pin "20") (pinfunction "VDD_PA_20") (pintype "bidirectional"))
    )
    (net (code "52") (name "Net-(C1-P$1)") (class "Default")
      (node (ref "C1") (pin "1") (pinfunction "P$1_1") (pintype "passive"))
      (node (ref "U7") (pin "28") (pinfunction "XC1_28") (pintype "input"))
      (node (ref "Y1") (pin "3") (pinfunction "2_3") (pintype "passive"))
    )
    (net (code "53") (name "Net-(C2-P$1)") (class "Default")
      (node (ref "C2") (pin "1") (pinfunction "P$1_1") (pintype "passive"))
      (node (ref "U7") (pin "27") (pinfunction "XC2_27") (pintype "output"))
      (node (ref "Y1") (pin "1") (pinfunction "1_1") (pintype "passive"))
    )
    (net (code "54") (name "Net-(C5-P$2)") (class "Default")
      (node (ref "C5") (pin "2") (pinfunction "P$2_2") (pintype "passive"))
      (node (ref "U7") (pin "4") (pinfunction "XL2_4") (pintype "output"))
      (node (ref "Y2") (pin "1") (pinfunction "1_1") (pintype "passive"))
    )
    (net (code "55") (name "Net-(C6-P$2)") (class "Default")
      (node (ref "C6") (pin "2") (pinfunction "P$2_2") (pintype "passive"))
      (node (ref "U7") (pin "5") (pinfunction "XL1_5") (pintype "input"))
      (node (ref "Y2") (pin "2") (pinfunction "2_2") (pintype "passive"))
    )
    (net (code "56") (name "Net-(C10-P$1)") (class "Default")
      (node (ref "C10") (pin "1") (pinfunction "P$1_1") (pintype "passive"))
      (node (ref "U7") (pin "2") (pinfunction "DEC1_2") (pintype "bidirectional"))
    )
    (net (code "57") (name "Net-(C11-P$1)") (class "Default")
      (node (ref "C11") (pin "1") (pinfunction "P$1_1") (pintype "passive"))
      (node (ref "U7") (pin "3") (pinfunction "DEC2_3") (pintype "bidirectional"))
    )
    (net (code "58") (name "Net-(C14-P$1)") (class "Default")
      (node (ref "C14") (pin "1") (pinfunction "P$1_1") (pintype "passive"))
      (node (ref "U8") (pin "1") (pinfunction "VREG_1") (pintype "output"))
    )
    (net (code "59") (name "Net-(C15-P$1)") (class "Default")
      (node (ref "C15") (pin "1") (pinfunction "P$1_1") (pintype "passive"))
      (node (ref "DISP1") (pin "3") (pinfunction "C2N_3") (pintype "input"))
    )
    (net (code "60") (name "Net-(C15-P$2)") (class "Default")
      (node (ref "C15") (pin "2") (pinfunction "P$2_2") (pintype "passive"))
      (node (ref "DISP1") (pin "2") (pinfunction "C2P_2") (pintype "input"))
    )
    (net (code "61") (name "Net-(C16-P$1)") (class "Default")
      (node (ref "C16") (pin "1") (pinfunction "P$1_1") (pintype "passive"))
      (node (ref "DISP1") (pin "5") (pinfunction "C1N_5") (pintype "input"))
    )
    (net (code "62") (name "Net-(C16-P$2)") (class "Default")
      (node (ref "C16") (pin "2") (pinfunction "P$2_2") (pintype "passive"))
      (node (ref "DISP1") (pin "4") (pinfunction "C1P_4") (pintype "input"))
    )
    (net (code "63") (name "Net-(C17-P$2)") (class "Default")
      (node (ref "C17") (pin "2") (pinfunction "P$2_2") (pintype "passive"))
      (node (ref "DISP1") (pin "28") (pinfunction "VCC_28") (pintype "power_in"))
    )
    (net (code "64") (name "Net-(C19-P$2)") (class "Default")
      (node (ref "C19") (pin "2") (pinfunction "P$2_2") (pintype "passive"))
      (node (ref "DISP1") (pin "27") (pinfunction "VCOMH_27") (pintype "output"))
    )
    (net (code "65") (name "Net-(C21-P$2)") (class "Default")
      (node (ref "C21") (pin "2") (pinfunction "P$2_2") (pintype "passive"))
      (node (ref "U4") (pin "5") (pinfunction "VDD_5") (pintype "bidirectional"))
    )
    (net (code "66") (name "Net-(C23-P$2)") (class "Default")
      (node (ref "C23") (pin "2") (pinfunction "P$2_2") (pintype "passive"))
      (node (ref "U1") (pin "43") (pinfunction "VDDCORE_43") (pintype "power_in"))
    )
    (net (code "67") (name "Net-(C24-P$1)") (class "Default")
      (node (ref "C24") (pin "1") (pinfunction "P$1_1") (pintype "passive"))
      (node (ref "U1") (pin "1") (pinfunction "PA00/EINT0/SERCOM1.0_1") (pintype "bidirectional"))
      (node (ref "X1") (pin "P$1") (pinfunction "P$1_P$1") (pintype "bidirectional"))
    )
    (net (code "68") (name "Net-(C25-P$1)") (class "Default")
      (node (ref "C25") (pin "1") (pinfunction "P$1_1") (pintype "passive"))
      (node (ref "U1") (pin "2") (pinfunction "PA01/EINT1/SERCOM1.1_2") (pintype "bidirectional"))
      (node (ref "X1") (pin "P$2") (pinfunction "P$2_P$2") (pintype "bidirectional"))
    )
    (net (code "69") (name "Net-(C27-P$2)") (class "Default")
      (node (ref "C27") (pin "2") (pinfunction "P$2_2") (pintype "passive"))
      (node (ref "U5") (pin "9") (pinfunction "CAP_9") (pintype "passive"))
    )
    (net (code "70") (name "Net-(DISP1-BS1)") (class "Default")
      (node (ref "DISP1") (pin "11") (pinfunction "BS1_11") (pintype "input"))
      (node (ref "R8") (pin "2") (pinfunction "2_2") (pintype "passive"))
    )
    (net (code "71") (name "Net-(DISP1-IREF)") (class "Default")
      (node (ref "DISP1") (pin "26") (pinfunction "IREF_26") (pintype "input"))
      (node (ref "R9") (pin "2") (pinfunction "2_2") (pintype "passive"))
    )
    (net (code "72") (name "Net-(EN-Pad1)") (class "Default")
      (node (ref "EN") (pin "1") (pinfunction "1_1") (pintype "passive"))
      (node (ref "R16") (pin "1") (pinfunction "1_1") (pintype "passive"))
    )
    (net (code "73") (name "Net-(L4-Pad2)") (class "Default")
      (node (ref "L4") (pin "2") (pinfunction "2_2") (pintype "passive"))
      (node (ref "L5") (pin "1") (pinfunction "1_1") (pintype "passive"))
    )
    (net (code "74") (name "Net-(U3-SDO)") (class "Default")
      (node (ref "R3") (pin "2") (pinfunction "2_2") (pintype "passive"))
      (node (ref "U3") (pin "5") (pinfunction "SDO_5") (pintype "output"))
    )
    (net (code "75") (name "Net-(U4-GPOUT)") (class "Default")
      (node (ref "R14") (pin "2") (pinfunction "2_2") (pintype "passive"))
      (node (ref "U4") (pin "12") (pinfunction "GPOUT_12") (pintype "bidirectional"))
    )
    (net (code "76") (name "Net-(U5-COM3)") (class "Default")
      (node (ref "R10") (pin "1") (pinfunction "1_1") (pintype "passive"))
      (node (ref "U5") (pin "17") (pinfunction "COM3_17") (pintype "bidirectional"))
    )
    (net (code "77") (name "Net-(U5-PS0)") (class "Default")
      (node (ref "R13") (pin "1") (pinfunction "1_1") (pintype "passive"))
      (node (ref "U5") (pin "6") (pinfunction "PS0_6") (pintype "input"))
    )
    (net (code "78") (name "Net-(U5-PS1)") (class "Default")
      (node (ref "R17") (pin "1") (pinfunction "1_1") (pintype "passive"))
      (node (ref "U5") (pin "5") (pinfunction "PS1_5") (pintype "input"))
    )
    (net (code "79") (name "Net-(U6-ILIM)") (class "Default")
      (node (ref "R15") (pin "1") (pinfunction "1_1") (pintype "passive"))
      (node (ref "U6") (pin "12") (pinfunction "ILIM_12") (pintype "bidirectional"))
    )
    (net (code "80") (name "Net-(U6-ISET)") (class "Default")
      (node (ref "R6") (pin "1") (pinfunction "1_1") (pintype "passive"))
      (node (ref "U6") (pin "16") (pinfunction "ISET_16") (pintype "bidirectional"))
    )
    (net (code "81") (name "Net-(U7B-DCC)") (class "Default")
      (node (ref "L4") (pin "1") (pinfunction "1_1") (pintype "passive"))
      (node (ref "U7") (pin "32") (pinfunction "DCC_32") (pintype "bidirectional"))
    )
    (net (code "82") (name "Net-(U7B-IREF)") (class "Default")
      (node (ref "R1") (pin "1") (pinfunction "1_1") (pintype "passive"))
      (node (ref "U7") (pin "25") (pinfunction "IREF_25") (pintype "output"))
    )
    (net (code "83") (name "Net-(U8-OUT+)") (class "Default")
      (node (ref "M+") (pin "P$1") (pinfunction "P$1_P$1") (pintype "bidirectional"))
      (node (ref "U8") (pin "7") (pinfunction "OUT+_7") (pintype "output"))
    )
    (net (code "84") (name "Net-(U8-OUT-)") (class "Default")
      (node (ref "M-") (pin "P$1") (pinfunction "P$1_P$1") (pintype "bidirectional"))
      (node (ref "U8") (pin "9") (pinfunction "OUT-_9") (pintype "output"))
    )
    (net (code "85") (name "SYSOFF") (class "Default")
      (node (ref "EN") (pin "2") (pinfunction "2_2") (pintype "passive"))
      (node (ref "U6") (pin "15") (pinfunction "SYSOFF_15") (pintype "bidirectional"))
    )
    (net (code "86") (name "TS") (class "Default")
      (node (ref "R20") (pin "1") (pinfunction "1_1") (pintype "passive"))
      (node (ref "U4") (pin "10") (pinfunction "BIN_10") (pintype "bidirectional"))
      (node (ref "U6") (pin "1") (pinfunction "TS_1") (pintype "bidirectional"))
    )
    (net (code "87") (name "VBAT") (class "Default")
      (node (ref "R16") (pin "2") (pinfunction "2_2") (pintype "passive"))
      (node (ref "R7") (pin "1") (pinfunction "1_1") (pintype "passive"))
      (node (ref "U4") (pin "7") (pinfunction "SRN_7") (pintype "bidirectional"))
      (node (ref "U6") (pin "2") (pinfunction "BAT_2") (pintype "bidirectional"))
      (node (ref "U6") (pin "3") (pinfunction "BAT_3") (pintype "bidirectional"))
    )
    (net (code "88") (name "VBUS") (class "Default")
      (node (ref "C22") (pin "2") (pinfunction "P$2_2") (pintype "passive"))
      (node (ref "JP1") (pin "VBUS") (pinfunction "VBUS_VBUS") (pintype "bidirectional"))
      (node (ref "U6") (pin "13") (pinfunction "IN_13") (pintype "bidirectional"))
    )
    (net (code "89") (name "unconnected-(B1-NC-Pad6)") (class "Default")
      (node (ref "B1") (pin "6") (pinfunction "NC_6") (pintype "no_connect"))
    )
    (net (code "90") (name "unconnected-(DISP1-D2{slash}I2C_SDA-Pad20)") (class "Default")
      (node (ref "DISP1") (pin "20") (pinfunction "D2/I2C_SDA_20") (pintype "bidirectional"))
    )
    (net (code "91") (name "unconnected-(DISP1-D3-Pad21)") (class "Default")
      (node (ref "DISP1") (pin "21") (pinfunction "D3_21") (pintype "bidirectional"))
    )
    (net (code "92") (name "unconnected-(DISP1-D4-Pad22)") (class "Default")
      (node (ref "DISP1") (pin "22") (pinfunction "D4_22") (pintype "bidirectional"))
    )
    (net (code "93") (name "unconnected-(DISP1-D5-Pad23)") (class "Default")
      (node (ref "DISP1") (pin "23") (pinfunction "D5_23") (pintype "bidirectional"))
    )
    (net (code "94") (name "unconnected-(DISP1-D6-Pad24)") (class "Default")
      (node (ref "DISP1") (pin "24") (pinfunction "D6_24") (pintype "bidirectional"))
    )
    (net (code "95") (name "unconnected-(DISP1-D7-Pad25)") (class "Default")
      (node (ref "DISP1") (pin "25") (pinfunction "D7_25") (pintype "bidirectional"))
    )
    (net (code "96") (name "unconnected-(DISP1-E{slash}RD-Pad17)") (class "Default")
      (node (ref "DISP1") (pin "17") (pinfunction "E/RD_17") (pintype "input"))
    )
    (net (code "97") (name "unconnected-(DISP1-NC-Pad7)") (class "Default")
      (node (ref "DISP1") (pin "7") (pinfunction "NC_7") (pintype "no_connect"))
    )
    (net (code "98") (name "unconnected-(DISP1-R{slash}W-Pad16)") (class "Default")
      (node (ref "DISP1") (pin "16") (pinfunction "R/W_16") (pintype "input"))
    )
    (net (code "99") (name "unconnected-(U1-PA13{slash}I13{slash}I2C{slash}SERCOM2+4.1-Pad22)") (class "Default")
      (node (ref "U1") (pin "22") (pinfunction "PA13/I13/I2C/SERCOM2+4.1_22") (pintype "bidirectional"))
    )
    (net (code "100") (name "unconnected-(U1-PA27{slash}I15-Pad39)") (class "Default")
      (node (ref "U1") (pin "39") (pinfunction "PA27/I15_39") (pintype "bidirectional"))
    )
    (net (code "101") (name "unconnected-(U1-PA28{slash}I8-Pad41)") (class "Default")
      (node (ref "U1") (pin "41") (pinfunction "PA28/I8_41") (pintype "bidirectional"))
    )
    (net (code "102") (name "unconnected-(U1-PB03{slash}I3{slash}AIN11{slash}SERCOM5.1-Pad48)") (class "Default")
      (node (ref "U1") (pin "48") (pinfunction "PB03/I3/AIN11/SERCOM5.1_48") (pintype "bidirectional"))
    )
    (net (code "103") (name "unconnected-(U1-PB22{slash}I6{slash}SERCOM5.2-Pad37)") (class "Default")
      (node (ref "U1") (pin "37") (pinfunction "PB22/I6/SERCOM5.2_37") (pintype "bidirectional"))
    )
    (net (code "104") (name "unconnected-(U1-PB23{slash}I7{slash}SERCOM5.3-Pad38)") (class "Default")
      (node (ref "U1") (pin "38") (pinfunction "PB23/I7/SERCOM5.3_38") (pintype "bidirectional"))
    )
    (net (code "105") (name "unconnected-(U2-FB{slash}NC-Pad4)") (class "Default")
      (node (ref "U2") (pin "4") (pinfunction "FB/NC_4") (pintype "input"))
    )
    (net (code "106") (name "unconnected-(U2-NC-Pad5)") (class "Default")
      (node (ref "U2") (pin "5") (pinfunction "NC_5") (pintype "no_connect"))
    )
    (net (code "107") (name "unconnected-(U2-NC_2-Pad2)") (class "Default")
      (node (ref "U2") (pin "2") (pinfunction "NC_2_2") (pintype "no_connect"))
    )
    (net (code "108") (name "unconnected-(U7B-NC-Pad15)") (class "Default")
      (node (ref "U7") (pin "15") (pinfunction "NC_15") (pintype "no_connect"))
    )
    (net (code "109") (name "unconnected-(U7B-RXD-Pad10)") (class "Default")
      (node (ref "U7") (pin "10") (pinfunction "RXD_10") (pintype "input"))
    )
    (net (code "110") (name "unconnected-(U7B-TXD-Pad7)") (class "Default")
      (node (ref "U7") (pin "7") (pinfunction "TXD_7") (pintype "output"))
    )
  )
)
